# MicronetToNMEAv3.net
KiCad netlist of a schematic drawn in EasyEDA Pro
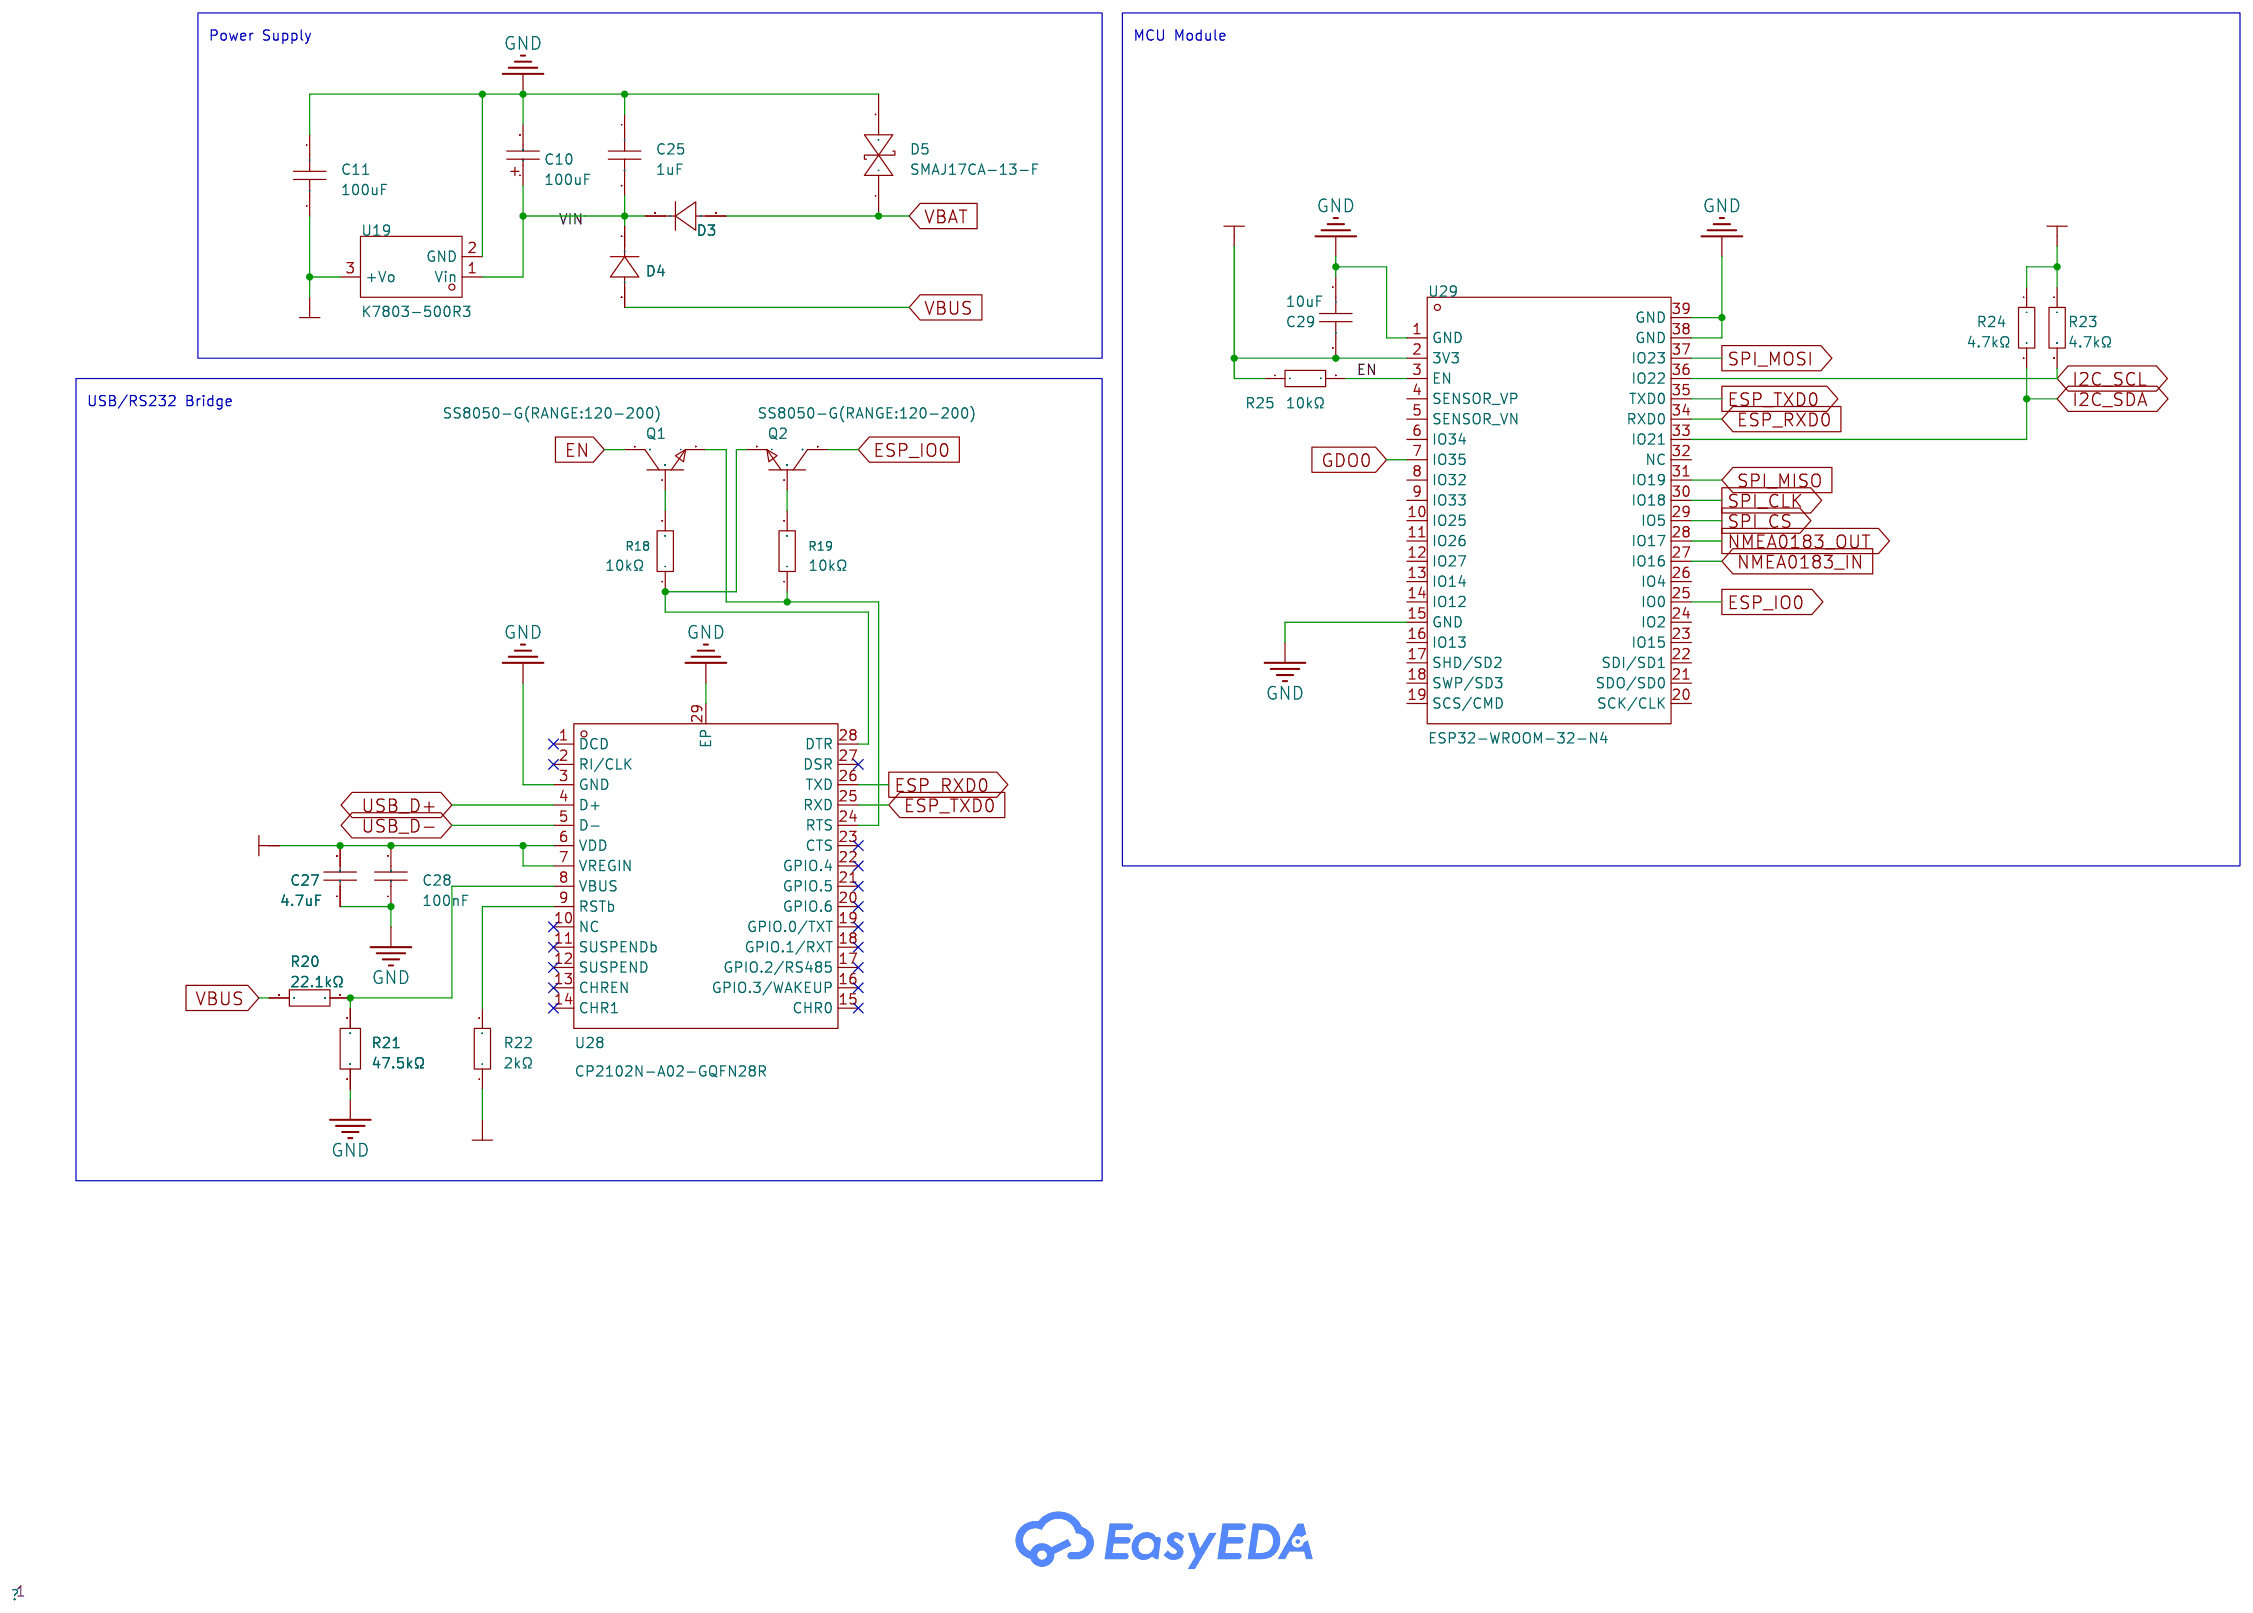
[diagram p0: MCU]
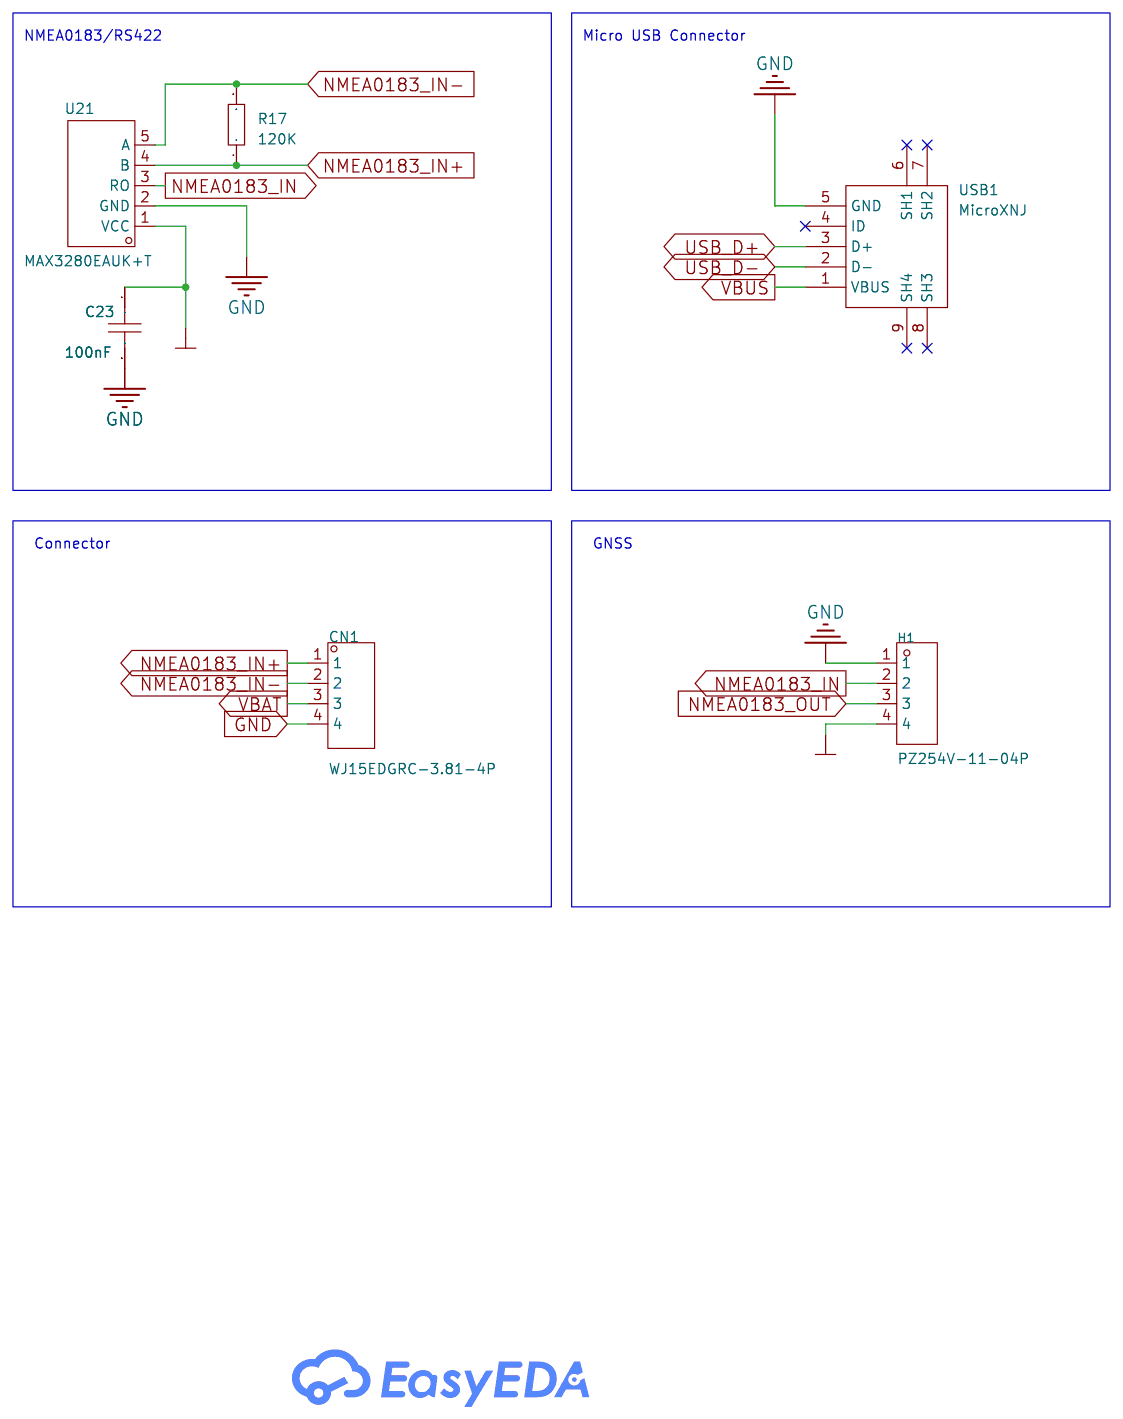
[diagram p1: Peripherals]
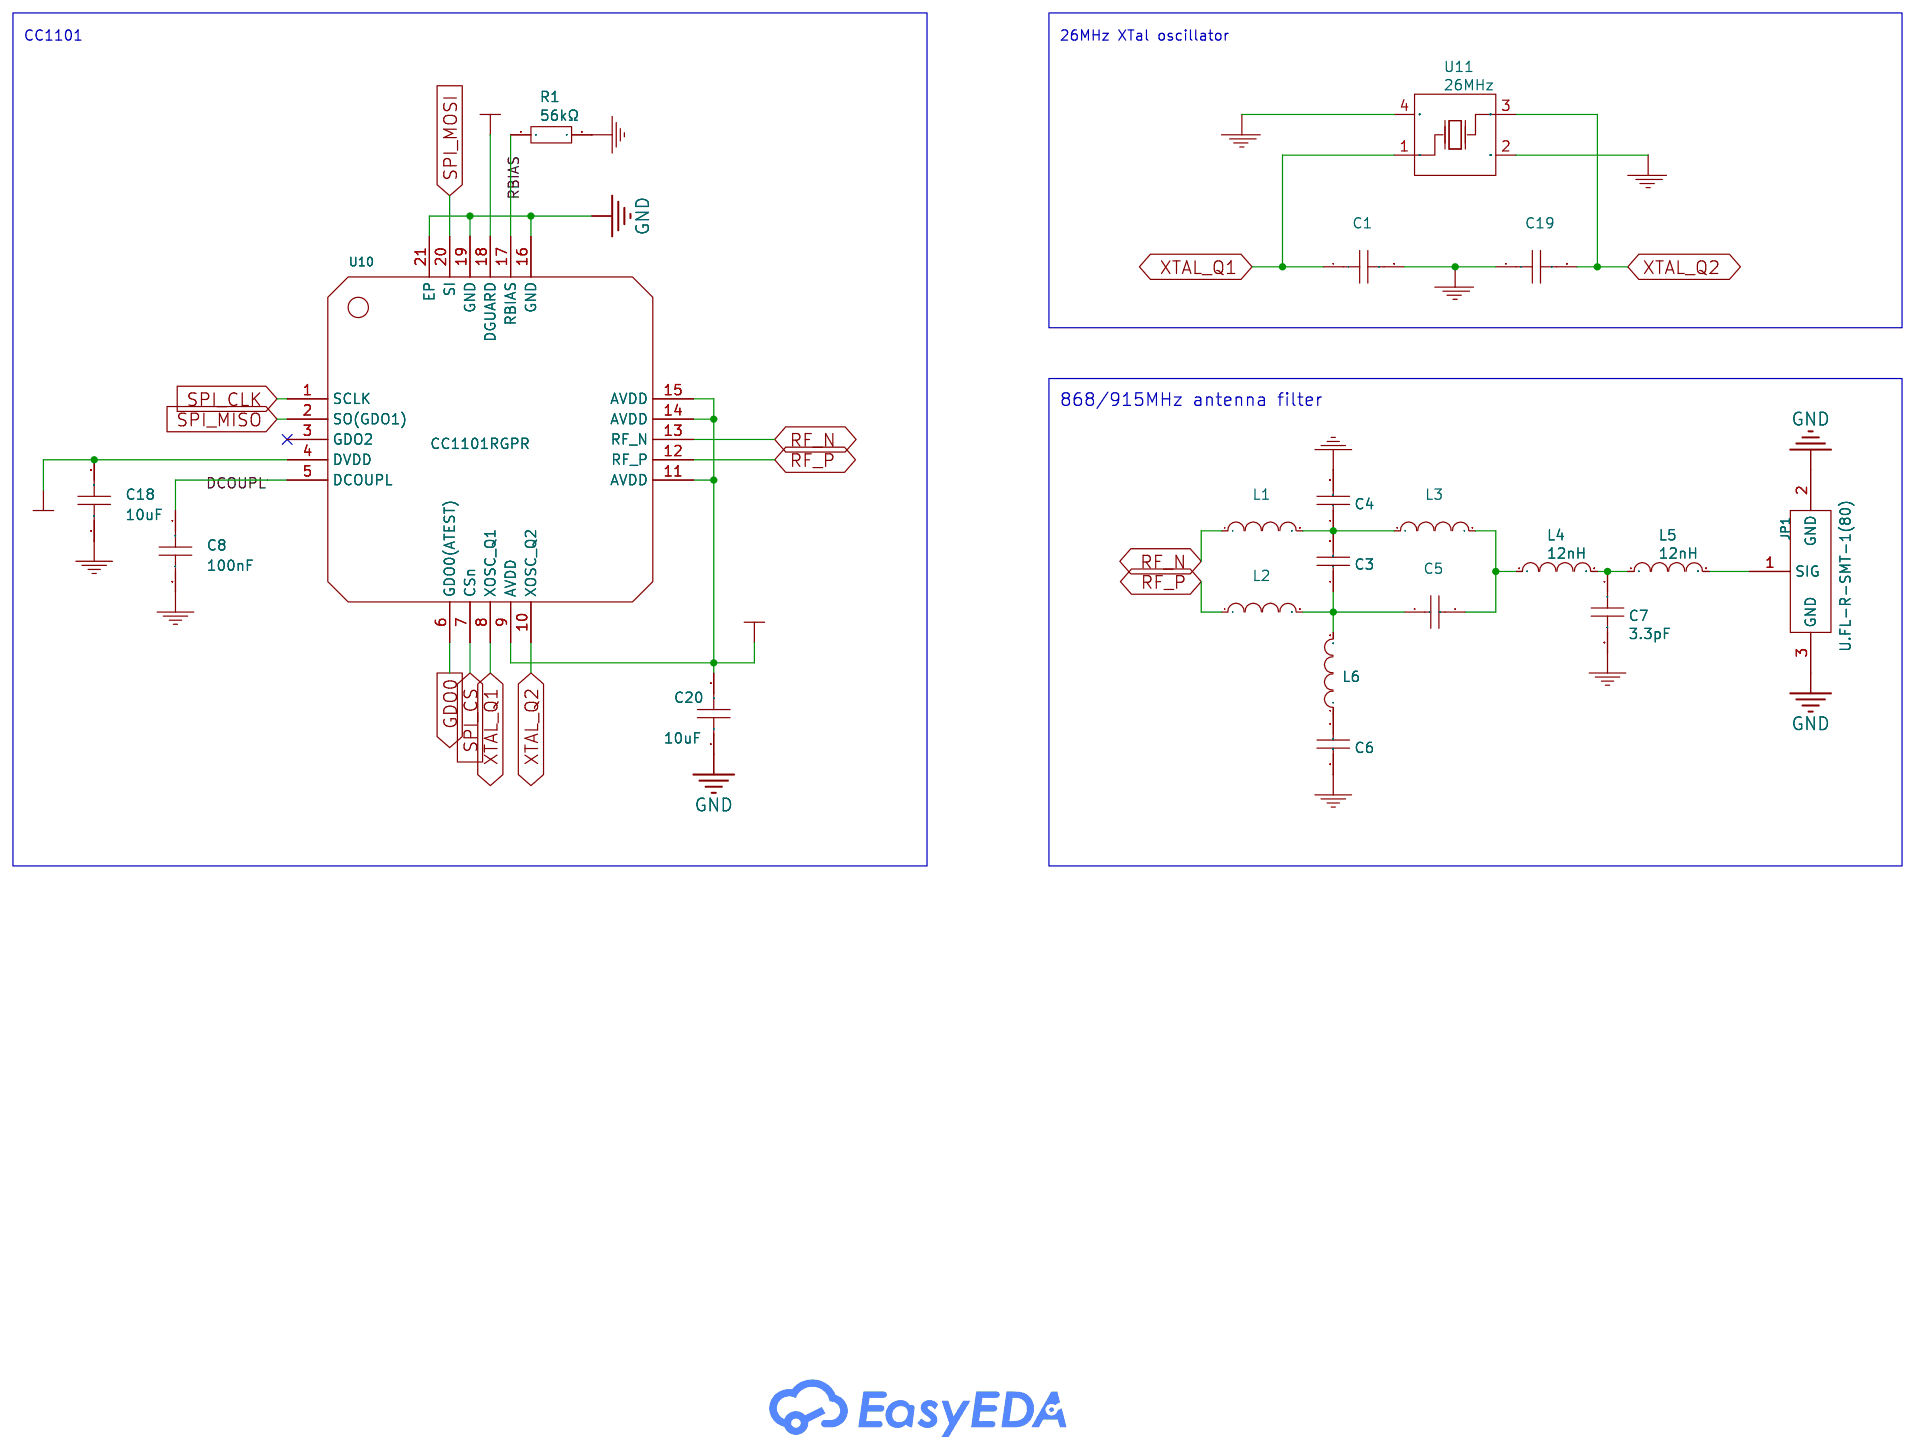
[diagram p2: Micronet RF]
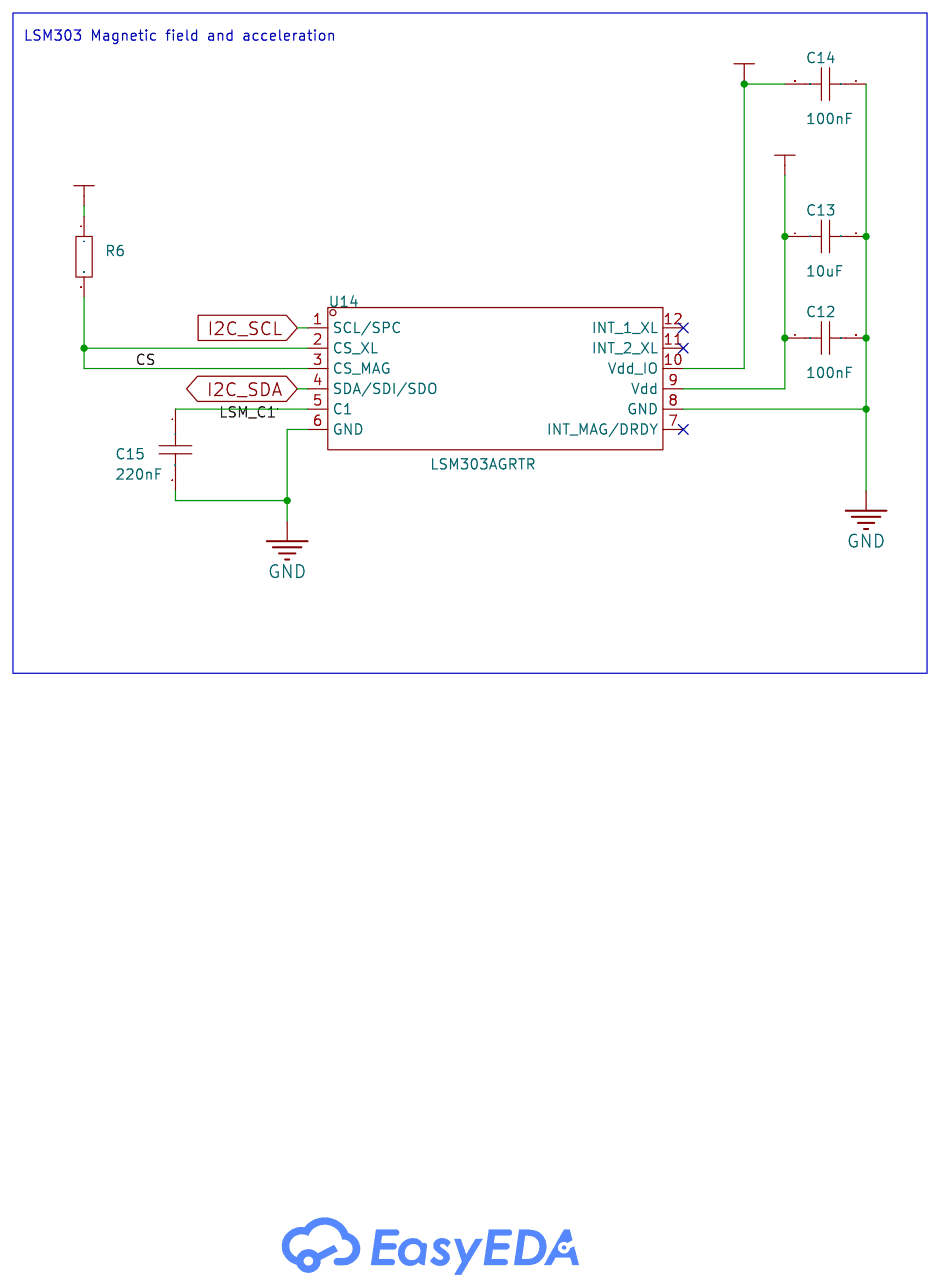
[diagram p3: Sensors]

(export (version "E")
  (design (tool "Eeschema 10.0.6"))
  (components
    (comp (ref "C10")
      (value "100uF")
      (fields (field (name "Manufacturer Part") "EEEFK1H101P") (field (name "Manufacturer") "PANASONIC(松下)"))
      (libsource (lib "easyedapro") (part "C_Ele_SMD"))
    )
    (comp (ref "C11")
      (value "100uF")
      (footprint "easyedapro:C0603")
      (fields
        (field (name "Manufacturer Part") "EMK325ABJ107MM-P")
        (field (name "Manufacturer") "TAIYO YUDEN(太诱)")
      )
      (libsource (lib "easyedapro") (part "CAP"))
    )
    (comp (ref "C25")
      (value "1uF")
      (footprint "easyedapro:C0603")
      (fields
        (field (name "Manufacturer Part") "GRM155R61H105KE05D")
        (field (name "Manufacturer") "muRata(村田)")
      )
      (libsource (lib "easyedapro") (part "CAP"))
    )
    (comp (ref "C27")
      (value "4.7uF")
      (footprint "easyedapro:C0603")
      (description "Capacitance:4.7uF Tolerance:±10% Tolerance:±10% Voltage Rating:6.3V Temperature Coefficient:X5R")
      (fields
        (field (name "Manufacturer Part") "CL10A475KQ8NNNC")
        (field (name "Manufacturer") "SAMSUNG(三星)")
      )
      (libsource (lib "easyedapro") (part "CL10A475KQ8NNNC"))
    )
    (comp (ref "C28")
      (value "100nF")
      (footprint "easyedapro:C0603")
      (description "Capacitance:100nF Tolerance:±10% Tolerance:±10% Voltage Rating:50V Temperature Coefficient:X7R")
      (fields (field (name "Manufacturer Part") "0603B104K500NT") (field (name "Manufacturer") "FH(风华)"))
      (libsource (lib "easyedapro") (part "0603B104K500NT"))
    )
    (comp (ref "C29")
      (value "10uF")
      (footprint "easyedapro:C0603")
      (fields
        (field (name "Manufacturer Part") "CL10A106MO8NQNC")
        (field (name "Manufacturer") "SAMSUNG(三星)")
      )
      (libsource (lib "easyedapro") (part "CAP"))
    )
    (comp (ref "D3")
      (value "1N4007WS")
      (fields (field (name "Manufacturer") "MDD(辰达半导体)"))
      (libsource (lib "easyedapro") (part "D_1N4007"))
    )
    (comp (ref "D4")
      (value "1N4007WS")
      (fields (field (name "Manufacturer") "MDD(辰达半导体)"))
      (libsource (lib "easyedapro") (part "D_1N4007"))
    )
    (comp (ref "D5")
      (value "SMAJ17CA-13-F")
      (footprint "easyedapro:SMA_L4.4-W2.6-LS5.0-BI")
      (fields (field (name "Manufacturer") "DIODES(美台)"))
      (libsource (lib "easyedapro") (part "SMAJ17CA-13-F"))
    )
    (comp (ref "Q1")
      (value "SS8050-G(RANGE:120-200)")
      (footprint "easyedapro:SOT-23-3_L2.9-W1.3-P1.90-LS2.4-BR")
      (fields (field (name "Manufacturer") "CJ(江苏长电/长晶)"))
      (libsource (lib "easyedapro") (part "SS8050-G"))
    )
    (comp (ref "Q2")
      (value "SS8050-G(RANGE:120-200)")
      (footprint "easyedapro:SOT-23-3_L2.9-W1.3-P1.90-LS2.4-BR")
      (fields (field (name "Manufacturer") "CJ(江苏长电/长晶)"))
      (libsource (lib "easyedapro") (part "SS8050-G"))
    )
    (comp (ref "R18")
      (value "10kΩ")
      (footprint "easyedapro:R0603")
      (fields (field (name "Manufacturer Part") "RMC060310K5%N") (field (name "Manufacturer") "Tyohm(幸亚电阻)"))
      (libsource (lib "easyedapro") (part "RMC060310K5%N"))
    )
    (comp (ref "R19")
      (value "10kΩ")
      (footprint "easyedapro:R0603")
      (fields (field (name "Manufacturer Part") "RMC060310K5%N") (field (name "Manufacturer") "Tyohm(幸亚电阻)"))
      (libsource (lib "easyedapro") (part "RMC060310K5%N"))
    )
    (comp (ref "R20")
      (value "22.1kΩ")
      (footprint "easyedapro:R0603")
      (fields (field (name "Manufacturer Part") "RC0603FR-0722K1L") (field (name "Manufacturer") "YAGEO(国巨)"))
      (libsource (lib "easyedapro") (part "RC0603FR-0722K1L"))
    )
    (comp (ref "R21")
      (value "47.5kΩ")
      (footprint "easyedapro:R0603")
      (fields (field (name "Manufacturer Part") "RT0603FRE0747K5L") (field (name "Manufacturer") "YAGEO(国巨)"))
      (libsource (lib "easyedapro") (part "RT0603FRE0747K5L"))
    )
    (comp (ref "R22")
      (value "2kΩ")
      (footprint "easyedapro:R0603")
      (fields (field (name "Manufacturer Part") "RTT03202JTP") (field (name "Manufacturer") "RALEC(旺诠)"))
      (libsource (lib "easyedapro") (part "RTT03202JTP"))
    )
    (comp (ref "R23")
      (value "4.7kΩ")
      (footprint "easyedapro:R0603")
      (fields
        (field (name "Manufacturer Part") "0402WGJ0472TCE")
        (field (name "Manufacturer") "UNI-ROYAL(厚声)")
      )
      (libsource (lib "easyedapro") (part "Res"))
    )
    (comp (ref "R24")
      (value "4.7kΩ")
      (footprint "easyedapro:R0603")
      (fields
        (field (name "Manufacturer Part") "0402WGJ0472TCE")
        (field (name "Manufacturer") "UNI-ROYAL(厚声)")
      )
      (libsource (lib "easyedapro") (part "Res"))
    )
    (comp (ref "R25")
      (value "10kΩ")
      (footprint "easyedapro:R0603")
      (fields
        (field (name "Manufacturer Part") "0402WGJ0103TCE")
        (field (name "Manufacturer") "UNI-ROYAL(厚声)")
      )
      (libsource (lib "easyedapro") (part "Res"))
    )
    (comp (ref "U19")
      (value "K7803-500R3")
      (footprint "easyedapro:PWRM-TH_K7803-500R3")
      (fields (field (name "Manufacturer") "YLPTEC(易川)"))
      (libsource (lib "easyedapro") (part "K7803-500R3_C5369643"))
    )
    (comp (ref "U28")
      (value "CP2102N-A02-GQFN28R")
      (footprint "easyedapro:QFN-28_L5.0-W5.0-P0.50-TL-EP3.3")
      (fields (field (name "Manufacturer") "SKYWORKS/SILICON LABS(芯科)"))
      (libsource (lib "easyedapro") (part "CP2102N-A02-GQFN28R"))
    )
    (comp (ref "U29")
      (value "ESP32-WROOM-32-N4")
      (footprint "easyedapro:WIFIM-SMD_ESP32-WROOM-32-N4")
      (fields (field (name "Manufacturer") "ESPRESSIF(乐鑫)"))
      (libsource (lib "easyedapro") (part "ESP32-WROOM-32"))
    )
    (comp (ref "C23")
      (value "100nF")
      (footprint "easyedapro:C0603")
      (fields
        (field (name "Manufacturer Part") "CL05B104KO5NNNC")
        (field (name "Manufacturer") "SAMSUNG(三星)")
      )
      (libsource (lib "easyedapro") (part "CAP"))
    )
    (comp (ref "CN1")
      (value "WJ15EDGRC-3.81-4P")
      (footprint "easyedapro:CONN-TH_WJ15EDGRC-3.81-4P")
      (fields (field (name "Manufacturer") "KANGNEX(康奈克斯电气)"))
      (libsource (lib "easyedapro") (part "WJ15EDGRC-3.81-4P"))
    )
    (comp (ref "H1")
      (value "PZ254V-11-04P")
      (footprint "easyedapro:HDR-TH_4P-P2.54-V-M")
      (fields (field (name "Manufacturer") "XFCN(兴飞)"))
      (libsource (lib "easyedapro") (part "PZ254V-11-04P_C2691448"))
    )
    (comp (ref "R17")
      (value "120K")
      (footprint "easyedapro:R0603")
      (libsource (lib "easyedapro") (part "Res"))
    )
    (comp (ref "U21")
      (value "MAX3280EAUK+T")
      (footprint "easyedapro:SOT-23-5_L3.0-W1.7-P0.95-LS2.8-BL")
      (fields (field (name "Manufacturer") "ADI(亚德诺)/MAXIM(美信)"))
      (libsource (lib "easyedapro") (part "MAX3280EAUK+T"))
    )
    (comp (ref "USB1")
      (value "MicroXNJ")
      (footprint "easyedapro:MICRO-USB-SMD_MICROXNJ")
      (fields (field (name "Manufacturer") "SHOU HAN(首韩)"))
      (libsource (lib "easyedapro") (part "MICROXNJ"))
    )
    (comp (ref "C1")
      (value "27pF")
      (footprint "easyedapro:C0402")
      (fields
        (field (name "Manufacturer Part") "GJM1555C1H270FB01D")
        (field (name "Manufacturer") "muRata(村田)")
      )
      (libsource (lib "easyedapro") (part "GJM1555C1H270FB01D"))
    )
    (comp (ref "C3")
      (value "1pF")
      (footprint "easyedapro:C0402")
      (fields
        (field (name "Manufacturer Part") "GRM1555C1H1R0CA01D")
        (field (name "Manufacturer") "muRata(村田)")
      )
      (libsource (lib "easyedapro") (part "GRM1555C1H1R0CA01D"))
    )
    (comp (ref "C4")
      (value "1.5pF")
      (footprint "easyedapro:C0402")
      (fields
        (field (name "Manufacturer Part") "GRM1555C1H1R5BA01D")
        (field (name "Manufacturer") "muRata(村田)")
      )
      (libsource (lib "easyedapro") (part "GRM1555C1H1R5BA01D"))
    )
    (comp (ref "C5")
      (value "1.5pF")
      (footprint "easyedapro:C0402")
      (fields
        (field (name "Manufacturer Part") "GRM1555C1H1R5BA01D")
        (field (name "Manufacturer") "muRata(村田)")
      )
      (libsource (lib "easyedapro") (part "GRM1555C1H1R5BA01D"))
    )
    (comp (ref "C6")
      (value "100pF")
      (footprint "easyedapro:C0402")
      (fields
        (field (name "Manufacturer Part") "GRM1555C1H101JA01D")
        (field (name "Manufacturer") "muRata(村田)")
      )
      (libsource (lib "easyedapro") (part "GRM1555C1H101JA01D"))
    )
    (comp (ref "C7")
      (value "3.3pF")
      (fields (field (name "Manufacturer") "muRata(村田)"))
      (libsource (lib "easyedapro") (part "3.3pF"))
    )
    (comp (ref "C8")
      (value "100nF")
      (footprint "easyedapro:C0402")
      (fields
        (field (name "Manufacturer Part") "GRM155R62A104KE14D")
        (field (name "Manufacturer") "muRata(村田)")
      )
      (libsource (lib "easyedapro") (part "GRM155R62A104KE14D"))
    )
    (comp (ref "C18")
      (value "10uF")
      (footprint "easyedapro:C0603")
      (fields
        (field (name "Manufacturer Part") "GRM155R61A106ME44D")
        (field (name "Manufacturer") "muRata(村田)")
      )
      (libsource (lib "easyedapro") (part "CAP"))
    )
    (comp (ref "C19")
      (value "27pF")
      (footprint "easyedapro:C0402")
      (fields
        (field (name "Manufacturer Part") "GJM1555C1H270FB01D")
        (field (name "Manufacturer") "muRata(村田)")
      )
      (libsource (lib "easyedapro") (part "GJM1555C1H270FB01D"))
    )
    (comp (ref "C20")
      (value "10uF")
      (footprint "easyedapro:C0603")
      (fields
        (field (name "Manufacturer Part") "GRM155R61A106ME44D")
        (field (name "Manufacturer") "muRata(村田)")
      )
      (libsource (lib "easyedapro") (part "CAP"))
    )
    (comp (ref "JP1")
      (value "U.FL-R-SMT-1(80)")
      (footprint "easyedapro:RF-SMD_FRF05002-JSS103M")
      (fields (field (name "Manufacturer") "HRS(广濑)"))
      (libsource (lib "easyedapro") (part "U.FL-R-SMT-1(80)"))
    )
    (comp (ref "L1")
      (value "12nH")
      (footprint "easyedapro:L0402")
      (fields (field (name "Manufacturer Part") "LQW15AN12NJ00D") (field (name "Manufacturer") "muRata(村田)"))
      (libsource (lib "easyedapro") (part "LQW15AN12NJ00D"))
    )
    (comp (ref "L2")
      (value "12nH")
      (footprint "easyedapro:L0402")
      (fields (field (name "Manufacturer Part") "LQW15AN12NJ00D") (field (name "Manufacturer") "muRata(村田)"))
      (libsource (lib "easyedapro") (part "LQW15AN12NJ00D"))
    )
    (comp (ref "L3") (value "18nH") (libsource (lib "easyedapro") (part "LQW15AN18NG00D")))
    (comp (ref "L4")
      (value "12nH")
      (footprint "easyedapro:L0402")
      (fields (field (name "Manufacturer Part") "LQW15AN12NG00D") (field (name "Manufacturer") "muRata(村田)"))
      (libsource (lib "easyedapro") (part "LQW15AN12NG00D"))
    )
    (comp (ref "L5")
      (value "12nH")
      (footprint "easyedapro:L0402")
      (fields (field (name "Manufacturer Part") "LQW15AN12NG00D") (field (name "Manufacturer") "muRata(村田)"))
      (libsource (lib "easyedapro") (part "LQW15AN12NG00D"))
    )
    (comp (ref "L6") (value "18nH") (libsource (lib "easyedapro") (part "LQW15AN18NG00D")))
    (comp (ref "R1")
      (value "56kΩ")
      (footprint "easyedapro:R0402")
      (fields (field (name "Manufacturer Part") "RK73H1ETTP5602F") (field (name "Manufacturer") "KOA"))
      (libsource (lib "easyedapro") (part "RK73H1ETTP5602F"))
    )
    (comp (ref "U10")
      (value "CC1101RGPR")
      (footprint "easyedapro:QFN-20_L4.0-W4.0-P0.5-TL-EP")
      (fields (field (name "Manufacturer") "TI(德州仪器)"))
      (libsource (lib "easyedapro") (part "CC1101RGPR"))
    )
    (comp (ref "U11") (value "26MHz") (libsource (lib "easyedapro") (part "26MHz")))
    (comp (ref "C12")
      (value "100nF")
      (footprint "easyedapro:C0603")
      (fields
        (field (name "Manufacturer Part") "CL05B104KO5NNNC")
        (field (name "Manufacturer") "SAMSUNG(三星)")
      )
      (libsource (lib "easyedapro") (part "CAP"))
    )
    (comp (ref "C13")
      (value "10uF")
      (footprint "easyedapro:C0603")
      (fields
        (field (name "Manufacturer Part") "GRM155R60J106ME44D")
        (field (name "Manufacturer") "muRata(村田)")
      )
      (libsource (lib "easyedapro") (part "CAP"))
    )
    (comp (ref "C14")
      (value "100nF")
      (footprint "easyedapro:C0603")
      (fields
        (field (name "Manufacturer Part") "CL05B104KO5NNNC")
        (field (name "Manufacturer") "SAMSUNG(三星)")
      )
      (libsource (lib "easyedapro") (part "CAP"))
    )
    (comp (ref "C15")
      (value "220nF")
      (footprint "easyedapro:C0603")
      (fields
        (field (name "Manufacturer Part") "CL05B224KO5NNNC")
        (field (name "Manufacturer") "SAMSUNG(三星)")
      )
      (libsource (lib "easyedapro") (part "CAP"))
    )
    (comp (ref "R6")
      (value "10kΩ")
      (footprint "easyedapro:R0603")
      (fields (field (name "Manufacturer") "UNI-ROYAL(厚声)"))
      (libsource (lib "easyedapro") (part "Res"))
    )
    (comp (ref "U14")
      (value "LSM303AGRTR")
      (footprint "easyedapro:LGA-12_L2.0-W2.0-P0.50-BL")
      (description "Sensor Type:加速度传感器 Operating Temperature:-40°C~+85°C Operating Temperature:-40°C~+85°C")
      (fields (field (name "Manufacturer") "ST(意法半导体)"))
      (libsource (lib "easyedapro") (part "LSM303AGRTR"))
    )
  )
  (nets
    (net (code "1") (name "+3.3V") (class "Default")
      (node (ref "C11") (pin "2") (pinfunction "2_2") (pintype "input"))
      (node (ref "C12") (pin "1") (pinfunction "1_1") (pintype "input"))
      (node (ref "C13") (pin "1") (pinfunction "1_1") (pintype "input"))
      (node (ref "C14") (pin "2") (pinfunction "2_2") (pintype "input"))
      (node (ref "C18") (pin "2") (pinfunction "2_2") (pintype "input"))
      (node (ref "C20") (pin "2") (pinfunction "2_2") (pintype "input"))
      (node (ref "C23") (pin "1") (pinfunction "1_1") (pintype "input"))
      (node (ref "C27") (pin "2") (pinfunction "2_2") (pintype "input"))
      (node (ref "C28") (pin "2") (pinfunction "2_2") (pintype "input"))
      (node (ref "C29") (pin "2") (pinfunction "2_2") (pintype "input"))
      (node (ref "H1") (pin "4") (pinfunction "4_4") (pintype "input"))
      (node (ref "R22") (pin "1") (pinfunction "1_1") (pintype "input"))
      (node (ref "R23") (pin "1") (pinfunction "1_1") (pintype "input"))
      (node (ref "R24") (pin "1") (pinfunction "1_1") (pintype "input"))
      (node (ref "R25") (pin "1") (pinfunction "1_1") (pintype "input"))
      (node (ref "R6") (pin "1") (pinfunction "1_1") (pintype "input"))
      (node (ref "U10") (pin "11") (pinfunction "AVDD_11") (pintype "input"))
      (node (ref "U10") (pin "14") (pinfunction "AVDD_14") (pintype "input"))
      (node (ref "U10") (pin "15") (pinfunction "AVDD_15") (pintype "input"))
      (node (ref "U10") (pin "18") (pinfunction "DGUARD_18") (pintype "input"))
      (node (ref "U10") (pin "4") (pinfunction "DVDD_4") (pintype "input"))
      (node (ref "U10") (pin "9") (pinfunction "AVDD_9") (pintype "input"))
      (node (ref "U14") (pin "10") (pinfunction "Vdd_IO_10") (pintype "unspecified"))
      (node (ref "U14") (pin "9") (pinfunction "Vdd_9") (pintype "unspecified"))
      (node (ref "U19") (pin "3") (pinfunction "+Vo_3") (pintype "unspecified"))
      (node (ref "U21") (pin "1") (pinfunction "VCC_1") (pintype "unspecified"))
      (node (ref "U28") (pin "6") (pinfunction "VDD_6") (pintype "unspecified"))
      (node (ref "U28") (pin "7") (pinfunction "VREGIN_7") (pintype "unspecified"))
      (node (ref "U29") (pin "2") (pinfunction "3V3_2") (pintype "unspecified"))
    )
    (net (code "2") (name "CS") (class "Default")
      (node (ref "R6") (pin "2") (pinfunction "2_2") (pintype "input"))
      (node (ref "U14") (pin "2") (pinfunction "CS_XL_2") (pintype "unspecified"))
      (node (ref "U14") (pin "3") (pinfunction "CS_MAG_3") (pintype "unspecified"))
    )
    (net (code "3") (name "DCOUPL") (class "Default")
      (node (ref "C8") (pin "1") (pinfunction "1_1") (pintype "input"))
      (node (ref "U10") (pin "5") (pinfunction "DCOUPL_5") (pintype "input"))
    )
    (net (code "4") (name "EN") (class "Default")
      (node (ref "Q1") (pin "3") (pinfunction "C_3") (pintype "input"))
      (node (ref "R25") (pin "2") (pinfunction "2_2") (pintype "input"))
      (node (ref "U29") (pin "3") (pinfunction "EN_3") (pintype "unspecified"))
    )
    (net (code "5") (name "ESP_IO0") (class "Default")
      (node (ref "Q2") (pin "3") (pinfunction "C_3") (pintype "input"))
      (node (ref "U29") (pin "25") (pinfunction "IO0_25") (pintype "unspecified"))
    )
    (net (code "6") (name "ESP_RXD0") (class "Default")
      (node (ref "U28") (pin "26") (pinfunction "TXD_26") (pintype "unspecified"))
      (node (ref "U29") (pin "34") (pinfunction "RXD0_34") (pintype "unspecified"))
    )
    (net (code "7") (name "ESP_TXD0") (class "Default")
      (node (ref "U28") (pin "25") (pinfunction "RXD_25") (pintype "unspecified"))
      (node (ref "U29") (pin "35") (pinfunction "TXD0_35") (pintype "unspecified"))
    )
    (net (code "8") (name "GDO0") (class "Default")
      (node (ref "U10") (pin "6") (pinfunction "GDO0(ATEST)_6") (pintype "input"))
      (node (ref "U29") (pin "7") (pinfunction "IO35_7") (pintype "unspecified"))
    )
    (net (code "9") (name "GND") (class "Default")
      (node (ref "C1") (pin "2") (pinfunction "2_2") (pintype "input"))
      (node (ref "C10") (pin "2") (pinfunction "2_2") (pintype "input"))
      (node (ref "C11") (pin "1") (pinfunction "1_1") (pintype "input"))
      (node (ref "C12") (pin "2") (pinfunction "2_2") (pintype "input"))
      (node (ref "C13") (pin "2") (pinfunction "2_2") (pintype "input"))
      (node (ref "C14") (pin "1") (pinfunction "1_1") (pintype "input"))
      (node (ref "C15") (pin "2") (pinfunction "2_2") (pintype "input"))
      (node (ref "C18") (pin "1") (pinfunction "1_1") (pintype "input"))
      (node (ref "C19") (pin "1") (pinfunction "1_1") (pintype "input"))
      (node (ref "C20") (pin "1") (pinfunction "1_1") (pintype "input"))
      (node (ref "C23") (pin "2") (pinfunction "2_2") (pintype "input"))
      (node (ref "C25") (pin "1") (pinfunction "1_1") (pintype "input"))
      (node (ref "C27") (pin "1") (pinfunction "1_1") (pintype "input"))
      (node (ref "C28") (pin "1") (pinfunction "1_1") (pintype "input"))
      (node (ref "C29") (pin "1") (pinfunction "1_1") (pintype "input"))
      (node (ref "C4") (pin "2") (pinfunction "2_2") (pintype "input"))
      (node (ref "C6") (pin "2") (pinfunction "2_2") (pintype "input"))
      (node (ref "C7") (pin "2") (pinfunction "2_2") (pintype "unspecified"))
      (node (ref "C8") (pin "2") (pinfunction "2_2") (pintype "input"))
      (node (ref "CN1") (pin "4") (pinfunction "4_4") (pintype "unspecified"))
      (node (ref "D5") (pin "2") (pinfunction "2_2") (pintype "unspecified"))
      (node (ref "H1") (pin "1") (pinfunction "1_1") (pintype "input"))
      (node (ref "JP1") (pin "2") (pinfunction "GND_2") (pintype "input"))
      (node (ref "JP1") (pin "3") (pinfunction "GND_3") (pintype "input"))
      (node (ref "R1") (pin "2") (pinfunction "2_2") (pintype "input"))
      (node (ref "R21") (pin "1") (pinfunction "1_1") (pintype "input"))
      (node (ref "U10") (pin "16") (pinfunction "GND_16") (pintype "input"))
      (node (ref "U10") (pin "19") (pinfunction "GND_19") (pintype "input"))
      (node (ref "U10") (pin "21") (pinfunction "EP_21") (pintype "input"))
      (node (ref "U11") (pin "2") (pinfunction "GND_2") (pintype "unspecified"))
      (node (ref "U11") (pin "4") (pinfunction "GND_4") (pintype "unspecified"))
      (node (ref "U14") (pin "6") (pinfunction "GND_6") (pintype "unspecified"))
      (node (ref "U14") (pin "8") (pinfunction "GND_8") (pintype "unspecified"))
      (node (ref "U19") (pin "2") (pinfunction "GND_2") (pintype "unspecified"))
      (node (ref "U21") (pin "2") (pinfunction "GND_2") (pintype "unspecified"))
      (node (ref "U28") (pin "29") (pinfunction "EP_29") (pintype "unspecified"))
      (node (ref "U28") (pin "3") (pinfunction "GND_3") (pintype "unspecified"))
      (node (ref "U29") (pin "1") (pinfunction "GND_1") (pintype "unspecified"))
      (node (ref "U29") (pin "15") (pinfunction "GND_15") (pintype "unspecified"))
      (node (ref "U29") (pin "38") (pinfunction "GND_38") (pintype "unspecified"))
      (node (ref "U29") (pin "39") (pinfunction "GND_39") (pintype "unspecified"))
      (node (ref "USB1") (pin "5") (pinfunction "GND_5") (pintype "unspecified"))
    )
    (net (code "10") (name "I2C_SCL") (class "Default")
      (node (ref "R23") (pin "2") (pinfunction "2_2") (pintype "input"))
      (node (ref "U14") (pin "1") (pinfunction "SCL/SPC_1") (pintype "unspecified"))
      (node (ref "U29") (pin "36") (pinfunction "IO22_36") (pintype "unspecified"))
    )
    (net (code "11") (name "I2C_SDA") (class "Default")
      (node (ref "R24") (pin "2") (pinfunction "2_2") (pintype "input"))
      (node (ref "U14") (pin "4") (pinfunction "SDA/SDI/SDO_4") (pintype "unspecified"))
      (node (ref "U29") (pin "33") (pinfunction "IO21_33") (pintype "unspecified"))
    )
    (net (code "12") (name "LSM_C1") (class "Default")
      (node (ref "C15") (pin "1") (pinfunction "1_1") (pintype "input"))
      (node (ref "U14") (pin "5") (pinfunction "C1_5") (pintype "unspecified"))
    )
    (net (code "13") (name "NMEA0183_IN") (class "Default")
      (node (ref "H1") (pin "2") (pinfunction "2_2") (pintype "input"))
      (node (ref "U21") (pin "3") (pinfunction "RO_3") (pintype "unspecified"))
      (node (ref "U29") (pin "27") (pinfunction "IO16_27") (pintype "unspecified"))
    )
    (net (code "14") (name "NMEA0183_IN+") (class "Default")
      (node (ref "CN1") (pin "1") (pinfunction "1_1") (pintype "unspecified"))
      (node (ref "R17") (pin "1") (pinfunction "1_1") (pintype "input"))
      (node (ref "U21") (pin "4") (pinfunction "B_4") (pintype "unspecified"))
    )
    (net (code "15") (name "NMEA0183_IN-") (class "Default")
      (node (ref "CN1") (pin "2") (pinfunction "2_2") (pintype "unspecified"))
      (node (ref "R17") (pin "2") (pinfunction "2_2") (pintype "input"))
      (node (ref "U21") (pin "5") (pinfunction "A_5") (pintype "unspecified"))
    )
    (net (code "16") (name "NMEA0183_OUT") (class "Default")
      (node (ref "H1") (pin "3") (pinfunction "3_3") (pintype "input"))
      (node (ref "U29") (pin "28") (pinfunction "IO17_28") (pintype "unspecified"))
    )
    (net (code "17") (name "Net-(C3-Pad1)") (class "Default")
      (node (ref "C3") (pin "1") (pinfunction "1_1") (pintype "input"))
      (node (ref "C5") (pin "2") (pinfunction "2_2") (pintype "input"))
      (node (ref "L2") (pin "2") (pinfunction "2_2") (pintype "input"))
      (node (ref "L6") (pin "2") (pinfunction "2_2") (pintype "input"))
    )
    (net (code "18") (name "Net-(C3-Pad2)") (class "Default")
      (node (ref "C3") (pin "2") (pinfunction "2_2") (pintype "input"))
      (node (ref "C4") (pin "1") (pinfunction "1_1") (pintype "input"))
      (node (ref "L1") (pin "2") (pinfunction "2_2") (pintype "input"))
      (node (ref "L3") (pin "1") (pinfunction "1_1") (pintype "input"))
    )
    (net (code "19") (name "Net-(C5-Pad1)") (class "Default")
      (node (ref "C5") (pin "1") (pinfunction "1_1") (pintype "input"))
      (node (ref "L3") (pin "2") (pinfunction "2_2") (pintype "input"))
      (node (ref "L4") (pin "1") (pinfunction "1_1") (pintype "unspecified"))
    )
    (net (code "20") (name "Net-(C6-Pad1)") (class "Default")
      (node (ref "C6") (pin "1") (pinfunction "1_1") (pintype "input"))
      (node (ref "L6") (pin "1") (pinfunction "1_1") (pintype "input"))
    )
    (net (code "21") (name "Net-(C7-Pad1)") (class "Default")
      (node (ref "C7") (pin "1") (pinfunction "1_1") (pintype "unspecified"))
      (node (ref "L4") (pin "2") (pinfunction "2_2") (pintype "unspecified"))
      (node (ref "L5") (pin "1") (pinfunction "1_1") (pintype "unspecified"))
    )
    (net (code "22") (name "Net-(JP1-SIG)") (class "Default")
      (node (ref "JP1") (pin "1") (pinfunction "SIG_1") (pintype "input"))
      (node (ref "L5") (pin "2") (pinfunction "2_2") (pintype "unspecified"))
    )
    (net (code "23") (name "Net-(Q1-B)") (class "Default")
      (node (ref "Q1") (pin "1") (pinfunction "B_1") (pintype "input"))
      (node (ref "R18") (pin "2") (pinfunction "2_2") (pintype "input"))
    )
    (net (code "24") (name "Net-(Q1-E)") (class "Default")
      (node (ref "Q1") (pin "2") (pinfunction "E_2") (pintype "input"))
      (node (ref "R19") (pin "1") (pinfunction "1_1") (pintype "input"))
      (node (ref "U28") (pin "24") (pinfunction "RTS_24") (pintype "unspecified"))
    )
    (net (code "25") (name "Net-(Q2-B)") (class "Default")
      (node (ref "Q2") (pin "1") (pinfunction "B_1") (pintype "input"))
      (node (ref "R19") (pin "2") (pinfunction "2_2") (pintype "input"))
    )
    (net (code "26") (name "Net-(Q2-E)") (class "Default")
      (node (ref "Q2") (pin "2") (pinfunction "E_2") (pintype "input"))
      (node (ref "R18") (pin "1") (pinfunction "1_1") (pintype "input"))
      (node (ref "U28") (pin "28") (pinfunction "DTR_28") (pintype "unspecified"))
    )
    (net (code "27") (name "Net-(U28-RSTb)") (class "Default")
      (node (ref "R22") (pin "2") (pinfunction "2_2") (pintype "input"))
      (node (ref "U28") (pin "9") (pinfunction "RSTb_9") (pintype "unspecified"))
    )
    (net (code "28") (name "Net-(U28-VBUS)") (class "Default")
      (node (ref "R20") (pin "1") (pinfunction "1_1") (pintype "input"))
      (node (ref "R21") (pin "2") (pinfunction "2_2") (pintype "input"))
      (node (ref "U28") (pin "8") (pinfunction "VBUS_8") (pintype "unspecified"))
    )
    (net (code "29") (name "RBIAS") (class "Default")
      (node (ref "R1") (pin "1") (pinfunction "1_1") (pintype "input"))
      (node (ref "U10") (pin "17") (pinfunction "RBIAS_17") (pintype "input"))
    )
    (net (code "30") (name "RF_N") (class "Default")
      (node (ref "L1") (pin "1") (pinfunction "1_1") (pintype "input"))
      (node (ref "U10") (pin "13") (pinfunction "RF_N_13") (pintype "input"))
    )
    (net (code "31") (name "RF_P") (class "Default")
      (node (ref "L2") (pin "1") (pinfunction "1_1") (pintype "input"))
      (node (ref "U10") (pin "12") (pinfunction "RF_P_12") (pintype "input"))
    )
    (net (code "32") (name "SPI_CLK") (class "Default")
      (node (ref "U10") (pin "1") (pinfunction "SCLK_1") (pintype "input"))
      (node (ref "U29") (pin "30") (pinfunction "IO18_30") (pintype "unspecified"))
    )
    (net (code "33") (name "SPI_CS") (class "Default")
      (node (ref "U10") (pin "7") (pinfunction "CSn_7") (pintype "input"))
      (node (ref "U29") (pin "29") (pinfunction "IO5_29") (pintype "unspecified"))
    )
    (net (code "34") (name "SPI_MISO") (class "Default")
      (node (ref "U10") (pin "2") (pinfunction "SO(GDO1)_2") (pintype "input"))
      (node (ref "U29") (pin "31") (pinfunction "IO19_31") (pintype "unspecified"))
    )
    (net (code "35") (name "SPI_MOSI") (class "Default")
      (node (ref "U10") (pin "20") (pinfunction "SI_20") (pintype "input"))
      (node (ref "U29") (pin "37") (pinfunction "IO23_37") (pintype "unspecified"))
    )
    (net (code "36") (name "USB_D+") (class "Default")
      (node (ref "U28") (pin "4") (pinfunction "D+_4") (pintype "unspecified"))
      (node (ref "USB1") (pin "3") (pinfunction "D+_3") (pintype "unspecified"))
    )
    (net (code "37") (name "USB_D-") (class "Default")
      (node (ref "U28") (pin "5") (pinfunction "D-_5") (pintype "unspecified"))
      (node (ref "USB1") (pin "2") (pinfunction "D-_2") (pintype "unspecified"))
    )
    (net (code "38") (name "VBAT") (class "Default")
      (node (ref "CN1") (pin "3") (pinfunction "3_3") (pintype "unspecified"))
      (node (ref "D3") (pin "2") (pinfunction "A_2") (pintype "input"))
      (node (ref "D5") (pin "1") (pinfunction "1_1") (pintype "unspecified"))
    )
    (net (code "39") (name "VBUS") (class "Default")
      (node (ref "D4") (pin "2") (pinfunction "A_2") (pintype "input"))
      (node (ref "R20") (pin "2") (pinfunction "2_2") (pintype "input"))
      (node (ref "USB1") (pin "1") (pinfunction "VBUS_1") (pintype "unspecified"))
    )
    (net (code "40") (name "VIN") (class "Default")
      (node (ref "C10") (pin "1") (pinfunction "1_1") (pintype "input"))
      (node (ref "C25") (pin "2") (pinfunction "2_2") (pintype "input"))
      (node (ref "D3") (pin "1") (pinfunction "K_1") (pintype "input"))
      (node (ref "D4") (pin "1") (pinfunction "K_1") (pintype "input"))
      (node (ref "U19") (pin "1") (pinfunction "Vin_1") (pintype "unspecified"))
    )
    (net (code "41") (name "XTAL_Q1") (class "Default")
      (node (ref "C1") (pin "1") (pinfunction "1_1") (pintype "input"))
      (node (ref "U10") (pin "8") (pinfunction "XOSC_Q1_8") (pintype "input"))
      (node (ref "U11") (pin "1") (pinfunction "OSC1_1") (pintype "unspecified"))
    )
    (net (code "42") (name "XTAL_Q2") (class "Default")
      (node (ref "C19") (pin "2") (pinfunction "2_2") (pintype "input"))
      (node (ref "U10") (pin "10") (pinfunction "XOSC_Q2_10") (pintype "input"))
      (node (ref "U11") (pin "3") (pinfunction "OSC2_3") (pintype "unspecified"))
    )
    (net (code "43") (name "unconnected-(U10-GDO2-Pad3)") (class "Default")
      (node (ref "U10") (pin "3") (pinfunction "GDO2_3") (pintype "input+no_connect"))
    )
    (net (code "44") (name "unconnected-(U14-INT_1_XL-Pad12)") (class "Default")
      (node (ref "U14") (pin "12") (pinfunction "INT_1_XL_12") (pintype "unspecified+no_connect"))
    )
    (net (code "45") (name "unconnected-(U14-INT_2_XL-Pad11)") (class "Default")
      (node (ref "U14") (pin "11") (pinfunction "INT_2_XL_11") (pintype "unspecified+no_connect"))
    )
    (net (code "46") (name "unconnected-(U14-INT_MAG{slash}DRDY-Pad7)") (class "Default")
      (node (ref "U14") (pin "7") (pinfunction "INT_MAG/DRDY_7") (pintype "unspecified+no_connect"))
    )
    (net (code "47") (name "unconnected-(U28-CHR0-Pad15)") (class "Default")
      (node (ref "U28") (pin "15") (pinfunction "CHR0_15") (pintype "unspecified+no_connect"))
    )
    (net (code "48") (name "unconnected-(U28-CHR1-Pad14)") (class "Default")
      (node (ref "U28") (pin "14") (pinfunction "CHR1_14") (pintype "unspecified+no_connect"))
    )
    (net (code "49") (name "unconnected-(U28-CHREN-Pad13)") (class "Default")
      (node (ref "U28") (pin "13") (pinfunction "CHREN_13") (pintype "unspecified+no_connect"))
    )
    (net (code "50") (name "unconnected-(U28-CTS-Pad23)") (class "Default")
      (node (ref "U28") (pin "23") (pinfunction "CTS_23") (pintype "unspecified+no_connect"))
    )
    (net (code "51") (name "unconnected-(U28-DCD-Pad1)") (class "Default")
      (node (ref "U28") (pin "1") (pinfunction "DCD_1") (pintype "unspecified+no_connect"))
    )
    (net (code "52") (name "unconnected-(U28-DSR-Pad27)") (class "Default")
      (node (ref "U28") (pin "27") (pinfunction "DSR_27") (pintype "unspecified+no_connect"))
    )
    (net (code "53") (name "unconnected-(U28-GPIO.0{slash}TXT-Pad19)") (class "Default")
      (node (ref "U28") (pin "19") (pinfunction "GPIO.0/TXT_19") (pintype "unspecified+no_connect"))
    )
    (net (code "54") (name "unconnected-(U28-GPIO.1{slash}RXT-Pad18)") (class "Default")
      (node (ref "U28") (pin "18") (pinfunction "GPIO.1/RXT_18") (pintype "unspecified+no_connect"))
    )
    (net (code "55") (name "unconnected-(U28-GPIO.2{slash}RS485-Pad17)") (class "Default")
      (node (ref "U28") (pin "17") (pinfunction "GPIO.2/RS485_17") (pintype "unspecified+no_connect"))
    )
    (net (code "56") (name "unconnected-(U28-GPIO.3{slash}WAKEUP-Pad16)") (class "Default")
      (node (ref "U28") (pin "16") (pinfunction "GPIO.3/WAKEUP_16") (pintype "unspecified+no_connect"))
    )
    (net (code "57") (name "unconnected-(U28-GPIO.4-Pad22)") (class "Default")
      (node (ref "U28") (pin "22") (pinfunction "GPIO.4_22") (pintype "unspecified+no_connect"))
    )
    (net (code "58") (name "unconnected-(U28-GPIO.5-Pad21)") (class "Default")
      (node (ref "U28") (pin "21") (pinfunction "GPIO.5_21") (pintype "unspecified+no_connect"))
    )
    (net (code "59") (name "unconnected-(U28-GPIO.6-Pad20)") (class "Default")
      (node (ref "U28") (pin "20") (pinfunction "GPIO.6_20") (pintype "unspecified+no_connect"))
    )
    (net (code "60") (name "unconnected-(U28-NC-Pad10)") (class "Default")
      (node (ref "U28") (pin "10") (pinfunction "NC_10") (pintype "unspecified+no_connect"))
    )
    (net (code "61") (name "unconnected-(U28-RI{slash}CLK-Pad2)") (class "Default")
      (node (ref "U28") (pin "2") (pinfunction "RI/CLK_2") (pintype "unspecified+no_connect"))
    )
    (net (code "62") (name "unconnected-(U28-SUSPEND-Pad12)") (class "Default")
      (node (ref "U28") (pin "12") (pinfunction "SUSPEND_12") (pintype "unspecified+no_connect"))
    )
    (net (code "63") (name "unconnected-(U28-SUSPENDb-Pad11)") (class "Default")
      (node (ref "U28") (pin "11") (pinfunction "SUSPENDb_11") (pintype "unspecified+no_connect"))
    )
    (net (code "64") (name "unconnected-(U29-IO2-Pad24)") (class "Default")
      (node (ref "U29") (pin "24") (pinfunction "IO2_24") (pintype "unspecified"))
    )
    (net (code "65") (name "unconnected-(U29-IO4-Pad26)") (class "Default")
      (node (ref "U29") (pin "26") (pinfunction "IO4_26") (pintype "unspecified"))
    )
    (net (code "66") (name "unconnected-(U29-IO12-Pad14)") (class "Default")
      (node (ref "U29") (pin "14") (pinfunction "IO12_14") (pintype "unspecified"))
    )
    (net (code "67") (name "unconnected-(U29-IO13-Pad16)") (class "Default")
      (node (ref "U29") (pin "16") (pinfunction "IO13_16") (pintype "unspecified"))
    )
    (net (code "68") (name "unconnected-(U29-IO14-Pad13)") (class "Default")
      (node (ref "U29") (pin "13") (pinfunction "IO14_13") (pintype "unspecified"))
    )
    (net (code "69") (name "unconnected-(U29-IO15-Pad23)") (class "Default")
      (node (ref "U29") (pin "23") (pinfunction "IO15_23") (pintype "unspecified"))
    )
    (net (code "70") (name "unconnected-(U29-IO25-Pad10)") (class "Default")
      (node (ref "U29") (pin "10") (pinfunction "IO25_10") (pintype "unspecified"))
    )
    (net (code "71") (name "unconnected-(U29-IO26-Pad11)") (class "Default")
      (node (ref "U29") (pin "11") (pinfunction "IO26_11") (pintype "unspecified"))
    )
    (net (code "72") (name "unconnected-(U29-IO27-Pad12)") (class "Default")
      (node (ref "U29") (pin "12") (pinfunction "IO27_12") (pintype "unspecified"))
    )
    (net (code "73") (name "unconnected-(U29-IO32-Pad8)") (class "Default")
      (node (ref "U29") (pin "8") (pinfunction "IO32_8") (pintype "unspecified"))
    )
    (net (code "74") (name "unconnected-(U29-IO33-Pad9)") (class "Default")
      (node (ref "U29") (pin "9") (pinfunction "IO33_9") (pintype "unspecified"))
    )
    (net (code "75") (name "unconnected-(U29-IO34-Pad6)") (class "Default")
      (node (ref "U29") (pin "6") (pinfunction "IO34_6") (pintype "unspecified"))
    )
    (net (code "76") (name "unconnected-(U29-NC-Pad32)") (class "Default")
      (node (ref "U29") (pin "32") (pinfunction "NC_32") (pintype "unspecified"))
    )
    (net (code "77") (name "unconnected-(U29-SCK{slash}CLK-Pad20)") (class "Default")
      (node (ref "U29") (pin "20") (pinfunction "SCK/CLK_20") (pintype "unspecified"))
    )
    (net (code "78") (name "unconnected-(U29-SCS{slash}CMD-Pad19)") (class "Default")
      (node (ref "U29") (pin "19") (pinfunction "SCS/CMD_19") (pintype "unspecified"))
    )
    (net (code "79") (name "unconnected-(U29-SDI{slash}SD1-Pad22)") (class "Default")
      (node (ref "U29") (pin "22") (pinfunction "SDI/SD1_22") (pintype "unspecified"))
    )
    (net (code "80") (name "unconnected-(U29-SDO{slash}SD0-Pad21)") (class "Default")
      (node (ref "U29") (pin "21") (pinfunction "SDO/SD0_21") (pintype "unspecified"))
    )
    (net (code "81") (name "unconnected-(U29-SENSOR_VN-Pad5)") (class "Default")
      (node (ref "U29") (pin "5") (pinfunction "SENSOR_VN_5") (pintype "unspecified"))
    )
    (net (code "82") (name "unconnected-(U29-SENSOR_VP-Pad4)") (class "Default")
      (node (ref "U29") (pin "4") (pinfunction "SENSOR_VP_4") (pintype "unspecified"))
    )
    (net (code "83") (name "unconnected-(U29-SHD{slash}SD2-Pad17)") (class "Default")
      (node (ref "U29") (pin "17") (pinfunction "SHD/SD2_17") (pintype "unspecified"))
    )
    (net (code "84") (name "unconnected-(U29-SWP{slash}SD3-Pad18)") (class "Default")
      (node (ref "U29") (pin "18") (pinfunction "SWP/SD3_18") (pintype "unspecified"))
    )
    (net (code "85") (name "unconnected-(USB1-ID-Pad4)") (class "Default")
      (node (ref "USB1") (pin "4") (pinfunction "ID_4") (pintype "unspecified+no_connect"))
    )
    (net (code "86") (name "unconnected-(USB1-SH1-Pad6)") (class "Default")
      (node (ref "USB1") (pin "6") (pinfunction "SH1_6") (pintype "unspecified+no_connect"))
    )
    (net (code "87") (name "unconnected-(USB1-SH2-Pad7)") (class "Default")
      (node (ref "USB1") (pin "7") (pinfunction "SH2_7") (pintype "unspecified+no_connect"))
    )
    (net (code "88") (name "unconnected-(USB1-SH3-Pad8)") (class "Default")
      (node (ref "USB1") (pin "8") (pinfunction "SH3_8") (pintype "unspecified+no_connect"))
    )
    (net (code "89") (name "unconnected-(USB1-SH4-Pad9)") (class "Default")
      (node (ref "USB1") (pin "9") (pinfunction "SH4_9") (pintype "unspecified+no_connect"))
    )
  )
)
